# SCREEN.net
KiCad netlist of a schematic drawn in Altium Designer
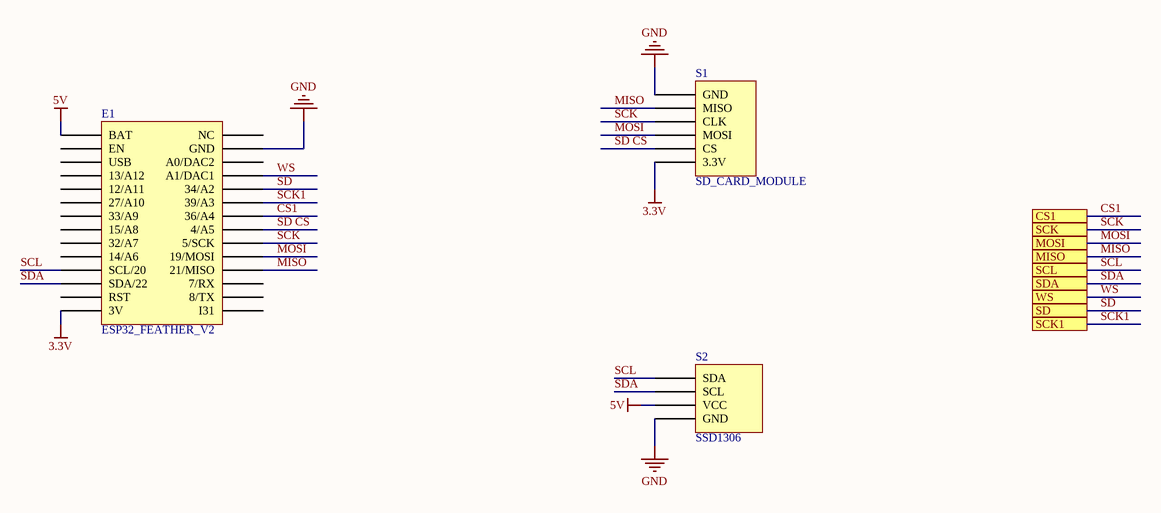
[diagram p0: SCREEN.SchDoc]

(export (version "E")
  (design (tool "Eeschema 10.0.6"))
  (components
    (comp (ref "E1")
      (value "ESP32_FEATHER_V2")
      (footprint "ESP32_FEATHER_V2")
      (description "ESP32 Feather V2")
      (libsource (lib "KHOEMACH_LIB") (part "ESP32_FEATHER_V2"))
    )
    (comp (ref "S1")
      (value "SD_CARD_MODULE")
      (footprint "MICRO_SD_CARD_MODULE")
      (libsource (lib "KHOEMACH_LIB") (part "SD_CARD_MODULE"))
    )
    (comp (ref "S2")
      (value "SSD1306")
      (footprint "SSD1306")
      (description "0.96 inch, 128x64")
      (libsource (lib "KHOEMACH_LIB") (part "SSD1306"))
    )
  )
  (nets
    (net (code "1") (name "/CS1") (class "Default")
      (node (ref "E1") (pin "8") (pinfunction "36/A4_8") (pintype "passive"))
    )
    (net (code "2") (name "/MISO") (class "Default")
      (node (ref "E1") (pin "4") (pinfunction "21/MISO_4") (pintype "passive"))
      (node (ref "S1") (pin "2") (pinfunction "MISO_2") (pintype "passive"))
    )
    (net (code "3") (name "/MOSI") (class "Default")
      (node (ref "E1") (pin "5") (pinfunction "19/MOSI_5") (pintype "passive"))
      (node (ref "S1") (pin "4") (pinfunction "MOSI_4") (pintype "passive"))
    )
    (net (code "4") (name "/SCK") (class "Default")
      (node (ref "E1") (pin "6") (pinfunction "5/SCK_6") (pintype "passive"))
      (node (ref "S1") (pin "3") (pinfunction "CLK_3") (pintype "passive"))
    )
    (net (code "5") (name "/SCK1") (class "Default")
      (node (ref "E1") (pin "9") (pinfunction "39/A3_9") (pintype "passive"))
    )
    (net (code "6") (name "/SCL") (class "Default")
      (node (ref "E1") (pin "27") (pinfunction "SCL/20_27") (pintype "passive"))
      (node (ref "S2") (pin "1") (pinfunction "SDA_1") (pintype "passive"))
    )
    (net (code "7") (name "/SD") (class "Default")
      (node (ref "E1") (pin "10") (pinfunction "34/A2_10") (pintype "passive"))
    )
    (net (code "8") (name "/SD CS") (class "Default")
      (node (ref "E1") (pin "7") (pinfunction "4/A5_7") (pintype "passive"))
      (node (ref "S1") (pin "5") (pinfunction "CS_5") (pintype "passive"))
    )
    (net (code "9") (name "/SDA") (class "Default")
      (node (ref "E1") (pin "28") (pinfunction "SDA/22_28") (pintype "passive"))
      (node (ref "S2") (pin "2") (pinfunction "SCL_2") (pintype "passive"))
    )
    (net (code "10") (name "/WS") (class "Default")
      (node (ref "E1") (pin "11") (pinfunction "A1/DAC1_11") (pintype "passive"))
    )
    (net (code "11") (name "3.3V") (class "Default")
      (node (ref "E1") (pin "15") (pinfunction "3V_15") (pintype "passive"))
      (node (ref "S1") (pin "6") (pinfunction "3.3V_6") (pintype "passive"))
    )
    (net (code "12") (name "5V") (class "Default")
      (node (ref "E1") (pin "17") (pinfunction "BAT_17") (pintype "passive"))
      (node (ref "S2") (pin "3") (pinfunction "VCC_3") (pintype "passive"))
    )
    (net (code "13") (name "GND") (class "Default")
      (node (ref "E1") (pin "13") (pinfunction "GND_13") (pintype "passive"))
      (node (ref "S1") (pin "1") (pinfunction "GND_1") (pintype "passive"))
      (node (ref "S2") (pin "4") (pinfunction "GND_4") (pintype "passive"))
    )
    (net (code "14") (name "unconnected-(E1-7{slash}RX-Pad3)") (class "Default")
      (node (ref "E1") (pin "3") (pinfunction "7/RX_3") (pintype "passive"))
    )
    (net (code "15") (name "unconnected-(E1-8{slash}TX-Pad2)") (class "Default")
      (node (ref "E1") (pin "2") (pinfunction "8/TX_2") (pintype "passive"))
    )
    (net (code "16") (name "unconnected-(E1-12{slash}A11-Pad21)") (class "Default")
      (node (ref "E1") (pin "21") (pinfunction "12/A11_21") (pintype "passive"))
    )
    (net (code "17") (name "unconnected-(E1-13{slash}A12-Pad20)") (class "Default")
      (node (ref "E1") (pin "20") (pinfunction "13/A12_20") (pintype "passive"))
    )
    (net (code "18") (name "unconnected-(E1-14{slash}A6-Pad26)") (class "Default")
      (node (ref "E1") (pin "26") (pinfunction "14/A6_26") (pintype "passive"))
    )
    (net (code "19") (name "unconnected-(E1-15{slash}A8-Pad24)") (class "Default")
      (node (ref "E1") (pin "24") (pinfunction "15/A8_24") (pintype "passive"))
    )
    (net (code "20") (name "unconnected-(E1-27{slash}A10-Pad22)") (class "Default")
      (node (ref "E1") (pin "22") (pinfunction "27/A10_22") (pintype "passive"))
    )
    (net (code "21") (name "unconnected-(E1-32{slash}A7-Pad25)") (class "Default")
      (node (ref "E1") (pin "25") (pinfunction "32/A7_25") (pintype "passive"))
    )
    (net (code "22") (name "unconnected-(E1-33{slash}A9-Pad23)") (class "Default")
      (node (ref "E1") (pin "23") (pinfunction "33/A9_23") (pintype "passive"))
    )
    (net (code "23") (name "unconnected-(E1-A0{slash}DAC2-Pad12)") (class "Default")
      (node (ref "E1") (pin "12") (pinfunction "A0/DAC2_12") (pintype "passive"))
    )
    (net (code "24") (name "unconnected-(E1-EN-Pad18)") (class "Default")
      (node (ref "E1") (pin "18") (pinfunction "EN_18") (pintype "passive"))
    )
    (net (code "25") (name "unconnected-(E1-I31-Pad1)") (class "Default")
      (node (ref "E1") (pin "1") (pinfunction "I31_1") (pintype "passive"))
    )
    (net (code "26") (name "unconnected-(E1-NC-Pad14)") (class "Default")
      (node (ref "E1") (pin "14") (pinfunction "NC_14") (pintype "passive"))
    )
    (net (code "27") (name "unconnected-(E1-RST-Pad16)") (class "Default")
      (node (ref "E1") (pin "16") (pinfunction "RST_16") (pintype "passive"))
    )
    (net (code "28") (name "unconnected-(E1-USB-Pad19)") (class "Default")
      (node (ref "E1") (pin "19") (pinfunction "USB_19") (pintype "passive"))
    )
  )
)
